# Mosfets.net
KiCad netlist of a schematic drawn in Altium Designer
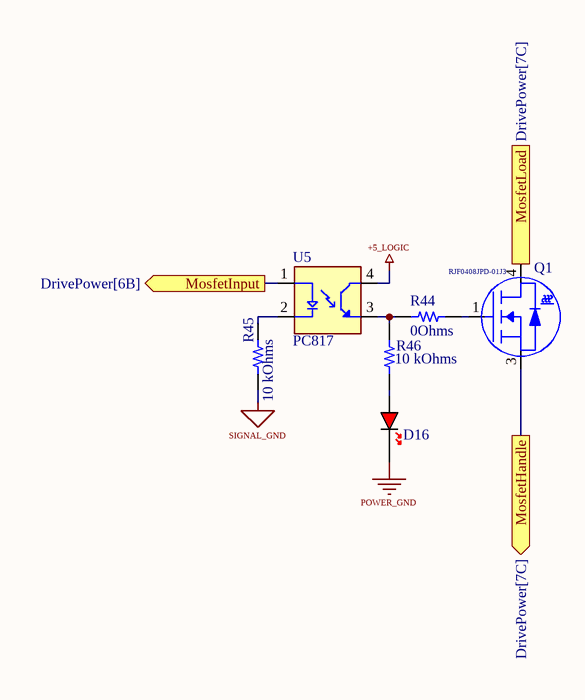
[diagram p0: Mosfets.SchDoc]

(export (version "E")
  (design (tool "Eeschema 10.0.6"))
  (components
    (comp (ref "D16")
      (value "RED")
      (footprint "LED_0603_RED")
      (description "Yellow Plox")
      (libsource (lib "Pedro_sch_lib") (part "LED_0603_RED"))
    )
    (comp (ref "Q1")
      (value "RJF0408JPD-01J3")
      (footprint "DPAKS_SC-63_PRSS0004ZD-C_REN")
      (description "No Description Available")
      (libsource (lib "RJF0408JPD-01J3") (part "RJF0408JPD-01J3"))
    )
    (comp (ref "R44")
      (value "0Ohms")
      (footprint "RES 0805_2012")
      (description "0805 35 AMP JUMPER")
      (fields (field (name "PART NUMBER") "JR0805X35E") (field (name "MANUFACTURER") "Ohmite"))
      (libsource (lib "Celestial Altium Library FIREWALL") (part "Resistor"))
    )
    (comp (ref "R45")
      (value "10 kOhms")
      (footprint "RES 0805_2012")
      (description "RES SMD 10K OHM 0.1% 1/4W 0805")
      (fields
        (field (name "PART NUMBER") "2176093-5")
        (field (name "MANUFACTURER") "TE Connectivity Passive Product")
      )
      (libsource (lib "Celestial Altium Library FIREWALL") (part "Resistor"))
    )
    (comp (ref "R46")
      (value "10 kOhms")
      (footprint "RES 0805_2012")
      (description "RES SMD 10K OHM 0.1% 1/4W 0805")
      (fields
        (field (name "PART NUMBER") "2176093-5")
        (field (name "MANUFACTURER") "TE Connectivity Passive Product")
      )
      (libsource (lib "Celestial Altium Library FIREWALL") (part "Resistor"))
    )
    (comp (ref "U5")
      (value "PC817")
      (footprint "PC817")
      (description "Optoisolator Transistor Output 5000Vrms 1 Channel 4-SMD")
      (fields (field (name "MP") "PC817XI") (field (name "MF") "Sharp Microelectronics"))
      (libsource (lib "Optocoupler SMD") (part "PC817"))
    )
  )
  (nets
    (net (code "1") (name "+5_LOGIC") (class "Default")
      (node (ref "U5") (pin "4") (pinfunction "CT_4") (pintype "passive"))
    )
    (net (code "2") (name "/MosfetHandle") (class "Default")
      (node (ref "Q1") (pin "3") (pinfunction "SOURCE_3") (pintype "passive"))
    )
    (net (code "3") (name "/MosfetInput") (class "Default")
      (node (ref "U5") (pin "1") (pinfunction "A_1") (pintype "passive"))
    )
    (net (code "4") (name "/MosfetLoad") (class "Default")
      (node (ref "Q1") (pin "4") (pinfunction "DRAIN_4") (pintype "passive"))
    )
    (net (code "5") (name "Net-(D16-PadA)") (class "Default")
      (node (ref "D16") (pin "A") (pinfunction "A_A") (pintype "passive"))
      (node (ref "R46") (pin "1") (pinfunction "1_1") (pintype "passive"))
    )
    (net (code "6") (name "Net-(Q1-GATE)") (class "Default")
      (node (ref "Q1") (pin "1") (pinfunction "GATE_1") (pintype "passive"))
      (node (ref "R44") (pin "2") (pinfunction "2_2") (pintype "passive"))
    )
    (net (code "7") (name "Net-(U5-C)") (class "Default")
      (node (ref "R45") (pin "2") (pinfunction "2_2") (pintype "passive"))
      (node (ref "U5") (pin "2") (pinfunction "C_2") (pintype "passive"))
    )
    (net (code "8") (name "Net-(U5-ET)") (class "Default")
      (node (ref "R44") (pin "1") (pinfunction "1_1") (pintype "passive"))
      (node (ref "R46") (pin "2") (pinfunction "2_2") (pintype "passive"))
      (node (ref "U5") (pin "3") (pinfunction "ET_3") (pintype "passive"))
    )
    (net (code "9") (name "POWER_GND") (class "Default")
      (node (ref "D16") (pin "K") (pinfunction "K_K") (pintype "passive"))
    )
    (net (code "10") (name "SIGNAL_GND") (class "Default")
      (node (ref "R45") (pin "1") (pinfunction "1_1") (pintype "passive"))
    )
  )
)
